# Sheet4.net
KiCad netlist of a schematic drawn in Altium Designer
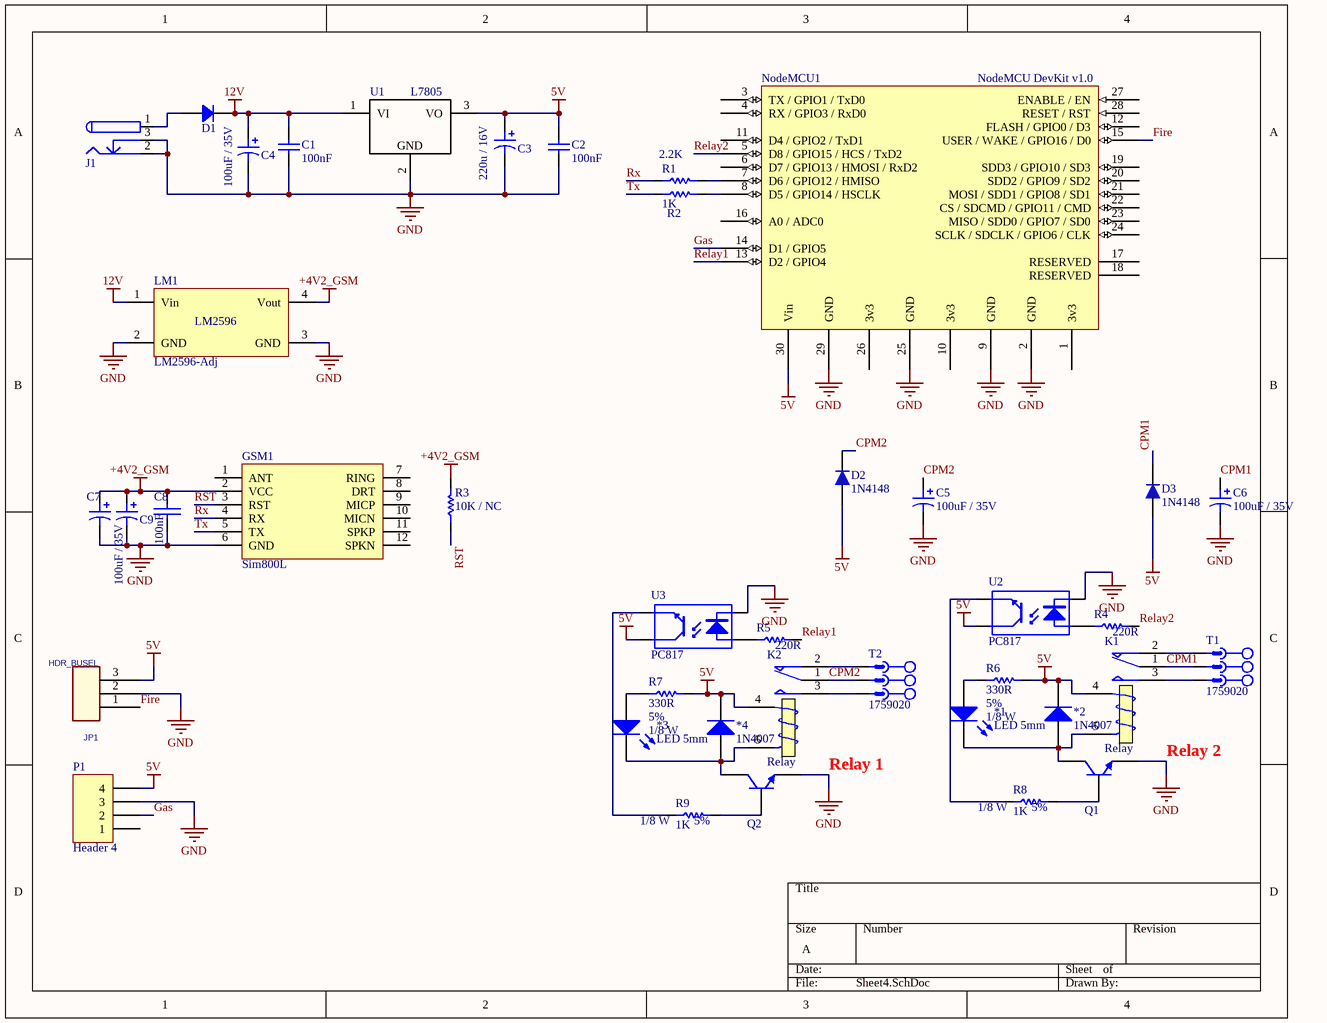
[diagram p0: Sheet4.SchDoc]

(export (version "E")
  (design (tool "Eeschema 10.0.6"))
  (components
    (comp (ref "*1") (value "LED 5mm") (footprint "led 5mm") (libsource (lib "General_04") (part "LED 5mm")))
    (comp (ref "*2") (value "1N4007") (footprint "1N4007") (libsource (lib "General_04") (part "1N4007")))
    (comp (ref "*3") (value "LED 5mm") (footprint "led 5mm") (libsource (lib "General_04") (part "LED 5mm")))
    (comp (ref "*4") (value "1N4007") (footprint "1N4007") (libsource (lib "General_04") (part "1N4007")))
    (comp (ref "C1")
      (value "100nF")
      (footprint "CAPC4817X12N")
      (description "CAP 1206")
      (fields (field (name "DESIGNER") "Abbas Basereh"))
      (libsource (lib "4_5924601381297062174") (part "CAP SMD 1206"))
    )
    (comp (ref "C2")
      (value "100nF")
      (footprint "CAPC4817X12N")
      (description "CAP 1206")
      (fields (field (name "DESIGNER") "Abbas Basereh"))
      (libsource (lib "4_5924601381297062174") (part "CAP SMD 1206"))
    )
    (comp (ref "C3")
      (value "220u / 16V")
      (footprint "Cap electrolitic radial 8x12-3.5")
      (description "Cap electrolitic radial")
      (fields (field (name "DESIGNER") "Abbas Basereh"))
      (libsource (lib "4_5924601381297062174") (part "Cap ELECTROLITIC TOTAL SIZE"))
    )
    (comp (ref "C4")
      (value "100uF / 35V")
      (footprint "Cap electrolitic radial 10x20-5")
      (description "Cap electrolitic radial")
      (fields (field (name "DESIGNER") "Abbas Basereh"))
      (libsource (lib "4_5924601381297062174") (part "Cap ELECTROLITIC TOTAL SIZE"))
    )
    (comp (ref "C5")
      (value "100uF / 35V")
      (footprint "Cap electrolitic radial 10x20-5")
      (description "Cap electrolitic radial")
      (fields (field (name "DESIGNER") "Abbas Basereh"))
      (libsource (lib "4_5924601381297062174") (part "Cap ELECTROLITIC TOTAL SIZE"))
    )
    (comp (ref "C6")
      (value "100uF / 35V")
      (footprint "Cap electrolitic radial 10x20-5")
      (description "Cap electrolitic radial")
      (fields (field (name "DESIGNER") "Abbas Basereh"))
      (libsource (lib "4_5924601381297062174") (part "Cap ELECTROLITIC TOTAL SIZE"))
    )
    (comp (ref "C7")
      (value "100uF50V")
      (footprint "Cap electrolitic radial 18x40-7.5")
      (description "Cap electrolitic radial")
      (fields (field (name "DESIGNER") "Abbas Basereh"))
      (libsource (lib "General 1") (part "Cap ELECTROLITIC TOTAL SIZE"))
    )
    (comp (ref "C8")
      (value "100nF")
      (footprint "Cap - 100nF")
      (description "Bipolar Capacitor")
      (fields (field (name "VOLTAGE") "100V") (field (name "DESIGNER") "Saeid Jorablo"))
      (libsource (lib "My Library (1)") (part "Cap-Bipolar"))
    )
    (comp (ref "C9")
      (value "100uF / 35V")
      (footprint "Cap electrolitic radial 10x20-5")
      (description "Cap electrolitic radial")
      (fields (field (name "DESIGNER") "Abbas Basereh"))
      (libsource (lib "4_5924601381297062174") (part "Cap ELECTROLITIC TOTAL SIZE"))
    )
    (comp (ref "D1")
      (value "1N4007")
      (footprint "DO41 P7.5MM")
      (description "Diode Standard 1000V 1A Through Hole DO-204AL (DO-41)")
      (libsource (lib "Diode") (part "1N4007 (THD)"))
    )
    (comp (ref "D2")
      (value "1N4148")
      (footprint "DO 35")
      (description "DIODE GEN PURP 100V 200MA DO35")
      (fields (field (name "PUBLISHER") "Abbas Basereh"))
      (libsource (lib "2017AbbasBasereh9365731239 -ver1") (part "1N4148"))
    )
    (comp (ref "D3")
      (value "1N4148")
      (footprint "DO 35")
      (description "DIODE GEN PURP 100V 200MA DO35")
      (fields (field (name "PUBLISHER") "Abbas Basereh"))
      (libsource (lib "2017AbbasBasereh9365731239 -ver1") (part "1N4148"))
    )
    (comp (ref "GSM1")
      (value "Sim800L")
      (footprint "Sim800L")
      (libsource (lib "Sim800L_Module") (part "Sim800L"))
    )
    (comp (ref "J1")
      (value "DC Power Jack")
      (footprint "DC Power Jack 1")
      (description "DC Power Jack. Center Pin 2.5mm. Diameter: 5.7mm")
      (fields (field (name "DESIGNER") "Ali Hafizi"))
      (libsource (lib "4_5965406465417019807") (part "DC Power Jack"))
    )
    (comp (ref "JP1")
      (value "HDR_BUSEL")
      (footprint "HDR_1x3")
      (description "header or jumper box")
      (libsource (lib "2017AbbasBasereh9365731239 -ver1") (part "Header 1x3"))
    )
    (comp (ref "K1")
      (value "Relay")
      (footprint "Relay 18.85x15.35x15.70")
      (description "SPDT Relay")
      (fields (field (name "DESIGNER") "Eng. Saeid Jorablo"))
      (libsource (lib "My_Library") (part "Relay"))
    )
    (comp (ref "K2")
      (value "Relay")
      (footprint "Relay 18.85x15.35x15.70")
      (description "SPDT Relay")
      (fields (field (name "DESIGNER") "Eng. Saeid Jorablo"))
      (libsource (lib "My_Library") (part "Relay"))
    )
    (comp (ref "LM1")
      (value "LM2596-Adj")
      (footprint "lm2596")
      (description "Designed By @Alixahedi")
      (libsource (lib "LM2596-Adj") (part "LM2596-Adj"))
    )
    (comp (ref "NodeMCU1")
      (value "NodeMCU DevKit v1.0")
      (footprint "NODEMCU")
      (libsource (lib "Personal-Altium-Library-master") (part "NodeMCU DevKit v1.0"))
    )
    (comp (ref "P1")
      (value "Header 4")
      (footprint "HDR1X4")
      (description "Header, 4-Pin")
      (fields (field (name "PUBLISHER") "Altium Limited"))
      (libsource (lib "4_5965406465417019807") (part "Header 4"))
    )
    (comp (ref "Q1")
      (value "BC547")
      (footprint "TO-92 BENT")
      (description "NPN Transistor")
      (fields (field (name "DESIGNER") "Abbas Basereh"))
      (libsource (lib "2017AbbasBasereh9365731239 -ver1") (part "BC547"))
    )
    (comp (ref "Q2")
      (value "BC547")
      (footprint "TO-92 BENT")
      (description "NPN Transistor")
      (fields (field (name "DESIGNER") "Abbas Basereh"))
      (libsource (lib "2017AbbasBasereh9365731239 -ver1") (part "BC547"))
    )
    (comp (ref "R1")
      (value "2.2K")
      (footprint "Res-(1/4)")
      (description "Resistor")
      (fields (field (name "TOLERANCE") "5%") (field (name "POWER") "1/8 W"))
      (libsource (lib "My_Library") (part "Resistor"))
    )
    (comp (ref "R2")
      (value "1K")
      (footprint "Res-(1/4)")
      (description "Resistor")
      (fields (field (name "TOLERANCE") "5%") (field (name "POWER") "1/8 W"))
      (libsource (lib "My_Library") (part "Resistor"))
    )
    (comp (ref "R3")
      (value "10K / NC")
      (footprint "Res-(1/4)")
      (description "Resistor")
      (fields (field (name "TOLERANCE") "5%") (field (name "POWER") "1/8 W"))
      (libsource (lib "My_Library") (part "Resistor"))
    )
    (comp (ref "R4")
      (value "220R")
      (footprint "Res-(1/4)")
      (description "Resistor")
      (libsource (lib "My_Library") (part "Resistor"))
    )
    (comp (ref "R5")
      (value "220R")
      (footprint "Res-(1/4)")
      (description "Resistor")
      (libsource (lib "My_Library") (part "Resistor"))
    )
    (comp (ref "R6")
      (value "330R")
      (footprint "Res-(1/4)")
      (description "Resistor")
      (fields (field (name "TOLERANCE") "5%") (field (name "POWER") "1/8 W"))
      (libsource (lib "My_Library") (part "Resistor"))
    )
    (comp (ref "R7")
      (value "330R")
      (footprint "Res-(1/4)")
      (description "Resistor")
      (fields (field (name "TOLERANCE") "5%") (field (name "POWER") "1/8 W"))
      (libsource (lib "My_Library") (part "Resistor"))
    )
    (comp (ref "R8")
      (value "1K")
      (footprint "Res-(1/4)")
      (description "Resistor")
      (fields (field (name "TOLERANCE") "5%") (field (name "POWER") "1/8 W"))
      (libsource (lib "My_Library") (part "Resistor"))
    )
    (comp (ref "R9")
      (value "1K")
      (footprint "Res-(1/4)")
      (description "Resistor")
      (fields (field (name "TOLERANCE") "5%") (field (name "POWER") "1/8 W"))
      (libsource (lib "My_Library") (part "Resistor"))
    )
    (comp (ref "T1")
      (value "1759020")
      (footprint "MSTB 2,5/3-G-5,08")
      (description "3 Pitch: 5.08 mm Color: green Contact surface: Tin Assembly")
      (fields
        (field (name "MANUFACTURER") "PHOENIX CONTACT")
        (field (name "VOLTAGE") "320 V")
        (field (name "DESIGNER") "ABBAS BASEREH")
      )
      (libsource (lib "2017AbbasBasereh9365731239 -ver1") (part "CON_Phoenix_MSTB_03"))
    )
    (comp (ref "T2")
      (value "1759020")
      (footprint "MSTB 2,5/3-G-5,08")
      (description "3 Pitch: 5.08 mm Color: green Contact surface: Tin Assembly")
      (fields
        (field (name "MANUFACTURER") "PHOENIX CONTACT")
        (field (name "VOLTAGE") "320 V")
        (field (name "DESIGNER") "ABBAS BASEREH")
      )
      (libsource (lib "2017AbbasBasereh9365731239 -ver1") (part "CON_Phoenix_MSTB_03"))
    )
    (comp (ref "U1")
      (value "L7805")
      (footprint "to220-123-v")
      (description "LINEAR REGULATOR 5.0V")
      (libsource (lib "General_05") (part "L7805-TO220"))
    )
    (comp (ref "U2")
      (value "PC817")
      (footprint "DIP4")
      (description "4-Pin Phototransistor Optocoupler")
      (libsource (lib "AltiumLib1") (part "OPTCOUPLER_01"))
    )
    (comp (ref "U3")
      (value "PC817")
      (footprint "DIP4")
      (description "4-Pin Phototransistor Optocoupler")
      (libsource (lib "AltiumLib1") (part "OPTCOUPLER_01"))
    )
  )
  (nets
    (net (code "1") (name "+4V2_GSM") (class "Default")
      (node (ref "C7") (pin "1") (pinfunction "1_1") (pintype "passive"))
      (node (ref "C8") (pin "1") (pinfunction "+_1") (pintype "passive"))
      (node (ref "C9") (pin "1") (pinfunction "1_1") (pintype "passive"))
      (node (ref "GSM1") (pin "2") (pinfunction "VCC_2") (pintype "passive"))
      (node (ref "LM1") (pin "4") (pinfunction "Vout_4") (pintype "passive"))
      (node (ref "R3") (pin "2") (pinfunction "2_2") (pintype "passive"))
    )
    (net (code "2") (name "/CPM1") (class "Default")
      (node (ref "C6") (pin "1") (pinfunction "1_1") (pintype "passive"))
      (node (ref "D3") (pin "2") (pintype "passive"))
      (node (ref "K1") (pin "1") (pinfunction "COM_1") (pintype "passive"))
      (node (ref "T1") (pin "2") (pinfunction "2_2") (pintype "passive"))
    )
    (net (code "3") (name "/CPM2") (class "Default")
      (node (ref "C5") (pin "1") (pinfunction "1_1") (pintype "passive"))
      (node (ref "D2") (pin "2") (pintype "passive"))
      (node (ref "K2") (pin "1") (pinfunction "COM_1") (pintype "passive"))
      (node (ref "T2") (pin "2") (pinfunction "2_2") (pintype "passive"))
    )
    (net (code "4") (name "/Fire") (class "Default")
      (node (ref "JP1") (pin "1") (pinfunction "1_1") (pintype "passive"))
      (node (ref "NodeMCU1") (pin "15") (pinfunction "USER_/_WAKE_/_GPIO16_/_D0_15") (pintype "bidirectional"))
    )
    (net (code "5") (name "/Gas") (class "Default")
      (node (ref "NodeMCU1") (pin "14") (pinfunction "D1_/_GPIO5_14") (pintype "bidirectional"))
      (node (ref "P1") (pin "2") (pinfunction "2_2") (pintype "passive"))
    )
    (net (code "6") (name "/RST") (class "Default")
      (node (ref "GSM1") (pin "3") (pinfunction "RST_3") (pintype "passive"))
      (node (ref "R3") (pin "1") (pinfunction "1_1") (pintype "passive"))
    )
    (net (code "7") (name "/Relay1") (class "Default")
      (node (ref "NodeMCU1") (pin "13") (pinfunction "D2_/_GPIO4_13") (pintype "bidirectional"))
      (node (ref "R5") (pin "2") (pinfunction "2_2") (pintype "passive"))
    )
    (net (code "8") (name "/Relay2") (class "Default")
      (node (ref "NodeMCU1") (pin "5") (pinfunction "D8_/_GPIO15_/_HCS_/_TxD2_5") (pintype "bidirectional"))
      (node (ref "R4") (pin "2") (pinfunction "2_2") (pintype "passive"))
    )
    (net (code "9") (name "/Rx") (class "Default")
      (node (ref "GSM1") (pin "4") (pinfunction "RX_4") (pintype "passive"))
      (node (ref "R1") (pin "1") (pinfunction "1_1") (pintype "passive"))
    )
    (net (code "10") (name "/Tx") (class "Default")
      (node (ref "GSM1") (pin "5") (pinfunction "TX_5") (pintype "passive"))
      (node (ref "R2") (pin "1") (pinfunction "1_1") (pintype "passive"))
    )
    (net (code "11") (name "5V") (class "Default")
      (node (ref "*2") (pin "2") (pinfunction "K_2") (pintype "passive"))
      (node (ref "*4") (pin "2") (pinfunction "K_2") (pintype "passive"))
      (node (ref "C2") (pin "1") (pinfunction "1_1") (pintype "passive"))
      (node (ref "C3") (pin "1") (pinfunction "1_1") (pintype "passive"))
      (node (ref "D2") (pin "1") (pintype "passive"))
      (node (ref "D3") (pin "1") (pintype "passive"))
      (node (ref "JP1") (pin "3") (pinfunction "3_3") (pintype "passive"))
      (node (ref "K1") (pin "4") (pinfunction "T1_4") (pintype "passive"))
      (node (ref "K2") (pin "4") (pinfunction "T1_4") (pintype "passive"))
      (node (ref "NodeMCU1") (pin "30") (pinfunction "Vin_30") (pintype "passive"))
      (node (ref "P1") (pin "4") (pinfunction "4_4") (pintype "passive"))
      (node (ref "R6") (pin "2") (pinfunction "2_2") (pintype "passive"))
      (node (ref "R7") (pin "2") (pinfunction "2_2") (pintype "passive"))
      (node (ref "U1") (pin "3") (pinfunction "VO_3") (pintype "passive"))
      (node (ref "U2") (pin "4") (pinfunction "C_4") (pintype "passive"))
      (node (ref "U3") (pin "4") (pinfunction "C_4") (pintype "passive"))
    )
    (net (code "12") (name "12V") (class "Default")
      (node (ref "C1") (pin "2") (pinfunction "2_2") (pintype "passive"))
      (node (ref "C4") (pin "1") (pinfunction "1_1") (pintype "passive"))
      (node (ref "D1") (pin "2") (pinfunction "2_2") (pintype "passive"))
      (node (ref "LM1") (pin "1") (pinfunction "Vin_1") (pintype "passive"))
      (node (ref "U1") (pin "1") (pinfunction "VI_1") (pintype "passive"))
    )
    (net (code "13") (name "GND") (class "Default")
      (node (ref "C1") (pin "1") (pinfunction "1_1") (pintype "passive"))
      (node (ref "C2") (pin "2") (pinfunction "2_2") (pintype "passive"))
      (node (ref "C3") (pin "2") (pinfunction "2_2") (pintype "passive"))
      (node (ref "C4") (pin "2") (pinfunction "2_2") (pintype "passive"))
      (node (ref "C5") (pin "2") (pinfunction "2_2") (pintype "passive"))
      (node (ref "C6") (pin "2") (pinfunction "2_2") (pintype "passive"))
      (node (ref "C7") (pin "2") (pinfunction "2_2") (pintype "passive"))
      (node (ref "C8") (pin "2") (pinfunction "-_2") (pintype "passive"))
      (node (ref "C9") (pin "2") (pinfunction "2_2") (pintype "passive"))
      (node (ref "GSM1") (pin "6") (pinfunction "GND_6") (pintype "passive"))
      (node (ref "J1") (pin "2") (pinfunction "2_2") (pintype "power_in"))
      (node (ref "J1") (pin "3") (pinfunction "3_3") (pintype "power_in"))
      (node (ref "JP1") (pin "2") (pinfunction "2_2") (pintype "passive"))
      (node (ref "LM1") (pin "2") (pinfunction "GND_2") (pintype "passive"))
      (node (ref "LM1") (pin "3") (pinfunction "GND_3") (pintype "passive"))
      (node (ref "NodeMCU1") (pin "2") (pinfunction "GND_2") (pintype "power_in"))
      (node (ref "NodeMCU1") (pin "25") (pinfunction "GND_25") (pintype "power_in"))
      (node (ref "NodeMCU1") (pin "29") (pinfunction "GND_29") (pintype "passive"))
      (node (ref "NodeMCU1") (pin "9") (pinfunction "GND_9") (pintype "power_in"))
      (node (ref "P1") (pin "3") (pinfunction "3_3") (pintype "passive"))
      (node (ref "Q1") (pin "3") (pinfunction "E_3") (pintype "passive"))
      (node (ref "Q2") (pin "3") (pinfunction "E_3") (pintype "passive"))
      (node (ref "U1") (pin "2") (pintype "passive"))
      (node (ref "U2") (pin "2") (pinfunction "K_2") (pintype "passive"))
      (node (ref "U3") (pin "2") (pinfunction "K_2") (pintype "passive"))
    )
    (net (code "14") (name "Net-(*1-A)") (class "Default")
      (node (ref "*1") (pin "1") (pinfunction "A_1") (pintype "passive"))
      (node (ref "R6") (pin "1") (pinfunction "1_1") (pintype "passive"))
    )
    (net (code "15") (name "Net-(*1-K)") (class "Default")
      (node (ref "*1") (pin "2") (pinfunction "K_2") (pintype "passive"))
      (node (ref "*2") (pin "1") (pinfunction "A_1") (pintype "passive"))
      (node (ref "K1") (pin "5") (pinfunction "T2_5") (pintype "passive"))
      (node (ref "Q1") (pin "1") (pinfunction "C_1") (pintype "passive"))
    )
    (net (code "16") (name "Net-(*3-A)") (class "Default")
      (node (ref "*3") (pin "1") (pinfunction "A_1") (pintype "passive"))
      (node (ref "R7") (pin "1") (pinfunction "1_1") (pintype "passive"))
    )
    (net (code "17") (name "Net-(*3-K)") (class "Default")
      (node (ref "*3") (pin "2") (pinfunction "K_2") (pintype "passive"))
      (node (ref "*4") (pin "1") (pinfunction "A_1") (pintype "passive"))
      (node (ref "K2") (pin "5") (pinfunction "T2_5") (pintype "passive"))
      (node (ref "Q2") (pin "1") (pinfunction "C_1") (pintype "passive"))
    )
    (net (code "18") (name "Net-(D1-Pad1)") (class "Default")
      (node (ref "D1") (pin "1") (pinfunction "1_1") (pintype "passive"))
      (node (ref "J1") (pin "1") (pinfunction "1_1") (pintype "power_in"))
    )
    (net (code "19") (name "Net-(K1-NC)") (class "Default")
      (node (ref "K1") (pin "2") (pinfunction "NC_2") (pintype "passive"))
      (node (ref "T1") (pin "3") (pinfunction "3_3") (pintype "passive"))
    )
    (net (code "20") (name "Net-(K1-NO)") (class "Default")
      (node (ref "K1") (pin "3") (pinfunction "NO_3") (pintype "passive"))
      (node (ref "T1") (pin "1") (pinfunction "1_1") (pintype "passive"))
    )
    (net (code "21") (name "Net-(K2-NC)") (class "Default")
      (node (ref "K2") (pin "2") (pinfunction "NC_2") (pintype "passive"))
      (node (ref "T2") (pin "3") (pinfunction "3_3") (pintype "passive"))
    )
    (net (code "22") (name "Net-(K2-NO)") (class "Default")
      (node (ref "K2") (pin "3") (pinfunction "NO_3") (pintype "passive"))
      (node (ref "T2") (pin "1") (pinfunction "1_1") (pintype "passive"))
    )
    (net (code "23") (name "Net-(NodeMCU1-D5_{slash}_GPIO14_{slash}_HSCLK)") (class "Default")
      (node (ref "NodeMCU1") (pin "8") (pinfunction "D5_/_GPIO14_/_HSCLK_8") (pintype "bidirectional"))
      (node (ref "R2") (pin "2") (pinfunction "2_2") (pintype "passive"))
    )
    (net (code "24") (name "Net-(NodeMCU1-D6_{slash}_GPIO12_{slash}_HMISO)") (class "Default")
      (node (ref "NodeMCU1") (pin "7") (pinfunction "D6_/_GPIO12_/_HMISO_7") (pintype "bidirectional"))
      (node (ref "R1") (pin "2") (pinfunction "2_2") (pintype "passive"))
    )
    (net (code "25") (name "Net-(Q1-B)") (class "Default")
      (node (ref "Q1") (pin "2") (pinfunction "B_2") (pintype "passive"))
      (node (ref "R8") (pin "2") (pinfunction "2_2") (pintype "passive"))
    )
    (net (code "26") (name "Net-(Q2-B)") (class "Default")
      (node (ref "Q2") (pin "2") (pinfunction "B_2") (pintype "passive"))
      (node (ref "R9") (pin "2") (pinfunction "2_2") (pintype "passive"))
    )
    (net (code "27") (name "Net-(U2-A)") (class "Default")
      (node (ref "R4") (pin "1") (pinfunction "1_1") (pintype "passive"))
      (node (ref "U2") (pin "1") (pinfunction "A_1") (pintype "passive"))
    )
    (net (code "28") (name "Net-(U2-E)") (class "Default")
      (node (ref "R8") (pin "1") (pinfunction "1_1") (pintype "passive"))
      (node (ref "U2") (pin "3") (pinfunction "E_3") (pintype "passive"))
    )
    (net (code "29") (name "Net-(U3-A)") (class "Default")
      (node (ref "R5") (pin "1") (pinfunction "1_1") (pintype "passive"))
      (node (ref "U3") (pin "1") (pinfunction "A_1") (pintype "passive"))
    )
    (net (code "30") (name "Net-(U3-E)") (class "Default")
      (node (ref "R9") (pin "1") (pinfunction "1_1") (pintype "passive"))
      (node (ref "U3") (pin "3") (pinfunction "E_3") (pintype "passive"))
    )
    (net (code "31") (name "unconnected-(GSM1-ANT-Pad1)") (class "Default")
      (node (ref "GSM1") (pin "1") (pinfunction "ANT_1") (pintype "passive"))
    )
    (net (code "32") (name "unconnected-(GSM1-DRT-Pad8)") (class "Default")
      (node (ref "GSM1") (pin "8") (pinfunction "DRT_8") (pintype "passive"))
    )
    (net (code "33") (name "unconnected-(GSM1-MICN-Pad10)") (class "Default")
      (node (ref "GSM1") (pin "10") (pinfunction "MICN_10") (pintype "passive"))
    )
    (net (code "34") (name "unconnected-(GSM1-MICP-Pad9)") (class "Default")
      (node (ref "GSM1") (pin "9") (pinfunction "MICP_9") (pintype "passive"))
    )
    (net (code "35") (name "unconnected-(GSM1-RING-Pad7)") (class "Default")
      (node (ref "GSM1") (pin "7") (pinfunction "RING_7") (pintype "passive"))
    )
    (net (code "36") (name "unconnected-(GSM1-SPKN-Pad12)") (class "Default")
      (node (ref "GSM1") (pin "12") (pinfunction "SPKN_12") (pintype "passive"))
    )
    (net (code "37") (name "unconnected-(GSM1-SPKP-Pad11)") (class "Default")
      (node (ref "GSM1") (pin "11") (pinfunction "SPKP_11") (pintype "passive"))
    )
    (net (code "38") (name "unconnected-(NodeMCU1-3v3-Pad1)") (class "Default")
      (node (ref "NodeMCU1") (pin "1") (pinfunction "3v3_1") (pintype "power_in"))
    )
    (net (code "39") (name "unconnected-(NodeMCU1-3v3-Pad10)") (class "Default")
      (node (ref "NodeMCU1") (pin "10") (pinfunction "3v3_10") (pintype "power_in"))
    )
    (net (code "40") (name "unconnected-(NodeMCU1-3v3-Pad26)") (class "Default")
      (node (ref "NodeMCU1") (pin "26") (pinfunction "3v3_26") (pintype "power_in"))
    )
    (net (code "41") (name "unconnected-(NodeMCU1-A0_{slash}_ADC0-Pad16)") (class "Default")
      (node (ref "NodeMCU1") (pin "16") (pinfunction "A0_/_ADC0_16") (pintype "bidirectional"))
    )
    (net (code "42") (name "unconnected-(NodeMCU1-CS_{slash}_SDCMD_{slash}_GPIO11_{slash}_CMD-Pad22)") (class "Default")
      (node (ref "NodeMCU1") (pin "22") (pinfunction "CS_/_SDCMD_/_GPIO11_/_CMD_22") (pintype "bidirectional"))
    )
    (net (code "43") (name "unconnected-(NodeMCU1-D4_{slash}_GPIO2_{slash}_TxD1-Pad11)") (class "Default")
      (node (ref "NodeMCU1") (pin "11") (pinfunction "D4_/_GPIO2_/_TxD1_11") (pintype "bidirectional"))
    )
    (net (code "44") (name "unconnected-(NodeMCU1-D7_{slash}_GPIO13_{slash}_HMOSI_{slash}_RxD2-Pad6)") (class "Default")
      (node (ref "NodeMCU1") (pin "6") (pinfunction "D7_/_GPIO13_/_HMOSI_/_RxD2_6") (pintype "bidirectional"))
    )
    (net (code "45") (name "unconnected-(NodeMCU1-ENABLE_{slash}_EN-Pad27)") (class "Default")
      (node (ref "NodeMCU1") (pin "27") (pinfunction "ENABLE_/_EN_27") (pintype "input"))
    )
    (net (code "46") (name "unconnected-(NodeMCU1-FLASH_{slash}_GPIO0_{slash}_D3-Pad12)") (class "Default")
      (node (ref "NodeMCU1") (pin "12") (pinfunction "FLASH_/_GPIO0_/_D3_12") (pintype "bidirectional"))
    )
    (net (code "47") (name "unconnected-(NodeMCU1-MISO_{slash}_SDD0_{slash}_GPIO7_{slash}_SD0-Pad23)") (class "Default")
      (node (ref "NodeMCU1") (pin "23") (pinfunction "MISO_/_SDD0_/_GPIO7_/_SD0_23") (pintype "bidirectional"))
    )
    (net (code "48") (name "unconnected-(NodeMCU1-MOSI_{slash}_SDD1_{slash}_GPIO8_{slash}_SD1-Pad21)") (class "Default")
      (node (ref "NodeMCU1") (pin "21") (pinfunction "MOSI_/_SDD1_/_GPIO8_/_SD1_21") (pintype "bidirectional"))
    )
    (net (code "49") (name "unconnected-(NodeMCU1-RESERVED-Pad17)") (class "Default")
      (node (ref "NodeMCU1") (pin "17") (pinfunction "RESERVED_17") (pintype "passive"))
    )
    (net (code "50") (name "unconnected-(NodeMCU1-RESERVED-Pad18)") (class "Default")
      (node (ref "NodeMCU1") (pin "18") (pinfunction "RESERVED_18") (pintype "passive"))
    )
    (net (code "51") (name "unconnected-(NodeMCU1-RESET_{slash}_RST-Pad28)") (class "Default")
      (node (ref "NodeMCU1") (pin "28") (pinfunction "RESET_/_RST_28") (pintype "input"))
    )
    (net (code "52") (name "unconnected-(NodeMCU1-RX_{slash}_GPIO3_{slash}_RxD0-Pad4)") (class "Default")
      (node (ref "NodeMCU1") (pin "4") (pinfunction "RX_/_GPIO3_/_RxD0_4") (pintype "bidirectional"))
    )
    (net (code "53") (name "unconnected-(NodeMCU1-SCLK_{slash}_SDCLK_{slash}_GPIO6_{slash}_CLK-Pad24)") (class "Default")
      (node (ref "NodeMCU1") (pin "24") (pinfunction "SCLK_/_SDCLK_/_GPIO6_/_CLK_24") (pintype "bidirectional"))
    )
    (net (code "54") (name "unconnected-(NodeMCU1-SDD2_{slash}_GPIO9_{slash}_SD2-Pad20)") (class "Default")
      (node (ref "NodeMCU1") (pin "20") (pinfunction "SDD2_/_GPIO9_/_SD2_20") (pintype "bidirectional"))
    )
    (net (code "55") (name "unconnected-(NodeMCU1-SDD3_{slash}_GPIO10_{slash}_SD3-Pad19)") (class "Default")
      (node (ref "NodeMCU1") (pin "19") (pinfunction "SDD3_/_GPIO10_/_SD3_19") (pintype "bidirectional"))
    )
    (net (code "56") (name "unconnected-(NodeMCU1-TX_{slash}_GPIO1_{slash}_TxD0-Pad3)") (class "Default")
      (node (ref "NodeMCU1") (pin "3") (pinfunction "TX_/_GPIO1_/_TxD0_3") (pintype "bidirectional"))
    )
    (net (code "57") (name "unconnected-(P1-Pad1)") (class "Default")
      (node (ref "P1") (pin "1") (pinfunction "1_1") (pintype "passive"))
    )
  )
)
